# gripper-board-rev1.net
KiCad netlist of a schematic drawn in EAGLE
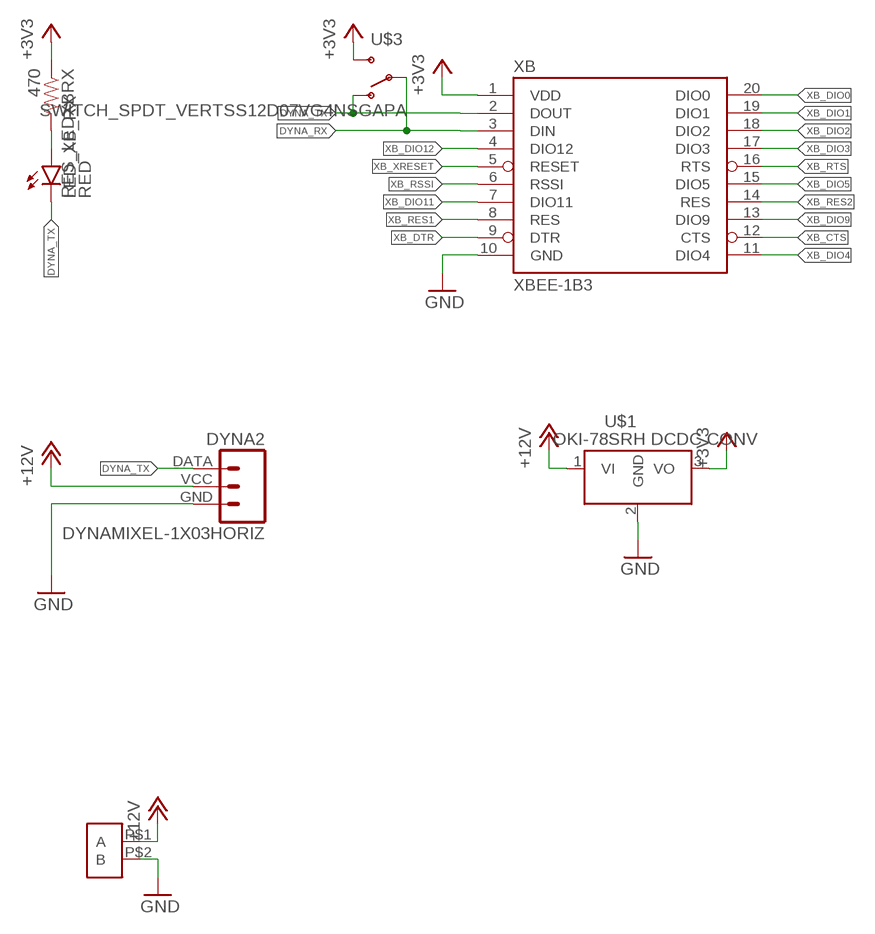
[diagram p0: schematic, sheet 1]

(export (version "E")
  (design (tool "Eeschema 10.0.6"))
  (components
    (comp (ref "DYNA2")
      (value "DYNAMIXEL-1X03HORIZ")
      (footprint "eagle-import:MLX-SPOX5268-3PIN")
      (fields (field (name "MFR") "Molex"))
      (libsource (lib "eagle-import") (part "DYNAMIXEL-1X03HORIZ"))
    )
    (comp (ref "LED_XB_RX")
      (value "RED")
      (footprint "eagle-import:LED-1206")
      (libsource (lib "eagle-import") (part "LED1206"))
    )
    (comp (ref "RES_LEDXBRX")
      (value "470")
      (footprint "eagle-import:1206")
      (libsource (lib "eagle-import") (part "RESISTOR1206"))
    )
    (comp (ref "U$1")
      (value "Q_OKI-78SR")
      (footprint "eagle-import:OKI-78SR_HORIZ")
      (libsource (lib "eagle-import") (part "Q_OKI-78SR"))
    )
    (comp (ref "U$2")
      (value "2POS_TERM_BLOCKPHOENIX-1935161")
      (footprint "eagle-import:PHOENIX-1935161")
      (libsource (lib "eagle-import") (part "2POS_TERM_BLOCKPHOENIX-1935161"))
    )
    (comp (ref "U$3")
      (value "SWITCH_SPDT_VERTSS12D07VG4NSGAPA")
      (footprint "eagle-import:C&K-SS12D07VG4NSGAPA")
      (libsource (lib "eagle-import") (part "SWITCH_SPDT_VERTSS12D07VG4NSGAPA"))
    )
    (comp (ref "XB")
      (value "XBEE-1B3")
      (footprint "eagle-import:XBEE-SMD")
      (libsource (lib "eagle-import") (part "XBEE-1B3"))
    )
  )
  (nets
    (net (code "1") (name "+3V3") (class "Default")
      (node (ref "RES_LEDXBRX") (pin "1") (pinfunction "1_1") (pintype "passive"))
      (node (ref "U$1") (pin "3") (pinfunction "VO_3") (pintype "bidirectional"))
      (node (ref "U$3") (pin "P$3") (pinfunction "S_P$3") (pintype "passive"))
      (node (ref "XB") (pin "1") (pinfunction "VDD_1") (pintype "power_in"))
    )
    (net (code "2") (name "+12V") (class "Default")
      (node (ref "DYNA2") (pin "VCC") (pinfunction "VCC_VCC") (pintype "passive"))
      (node (ref "U$1") (pin "1") (pinfunction "VI_1") (pintype "bidirectional"))
      (node (ref "U$2") (pin "P$1") (pinfunction "A_P$1") (pintype "bidirectional"))
    )
    (net (code "3") (name "DYNA_RX") (class "Default")
      (node (ref "U$3") (pin "P$2") (pinfunction "P_P$2") (pintype "passive"))
      (node (ref "XB") (pin "3") (pinfunction "DIN_3") (pintype "input"))
    )
    (net (code "4") (name "DYNA_TX") (class "Default")
      (node (ref "DYNA2") (pin "DATA") (pinfunction "DATA_DATA") (pintype "passive"))
      (node (ref "LED_XB_RX") (pin "C") (pinfunction "C_C") (pintype "passive"))
      (node (ref "U$3") (pin "P$1") (pinfunction "O_P$1") (pintype "passive"))
      (node (ref "XB") (pin "2") (pinfunction "DOUT_2") (pintype "output"))
    )
    (net (code "5") (name "GND") (class "Default")
      (node (ref "DYNA2") (pin "GND") (pinfunction "GND_GND") (pintype "passive"))
      (node (ref "U$1") (pin "2") (pinfunction "GND_2") (pintype "bidirectional"))
      (node (ref "U$2") (pin "P$2") (pinfunction "B_P$2") (pintype "bidirectional"))
      (node (ref "XB") (pin "10") (pinfunction "GND_10") (pintype "power_in"))
    )
    (net (code "6") (name "Net-(LED_XB_RX-PadA)") (class "Default")
      (node (ref "LED_XB_RX") (pin "A") (pinfunction "A_A") (pintype "passive"))
      (node (ref "RES_LEDXBRX") (pin "2") (pinfunction "2_2") (pintype "passive"))
    )
    (net (code "7") (name "XB_CTS") (class "Default")
      (node (ref "XB") (pin "12") (pinfunction "CTS_12") (pintype "output"))
    )
    (net (code "8") (name "XB_DIO0") (class "Default")
      (node (ref "XB") (pin "20") (pinfunction "DIO0_20") (pintype "bidirectional"))
    )
    (net (code "9") (name "XB_DIO1") (class "Default")
      (node (ref "XB") (pin "19") (pinfunction "DIO1_19") (pintype "bidirectional"))
    )
    (net (code "10") (name "XB_DIO2") (class "Default")
      (node (ref "XB") (pin "18") (pinfunction "DIO2_18") (pintype "bidirectional"))
    )
    (net (code "11") (name "XB_DIO3") (class "Default")
      (node (ref "XB") (pin "17") (pinfunction "DIO3_17") (pintype "bidirectional"))
    )
    (net (code "12") (name "XB_DIO4") (class "Default")
      (node (ref "XB") (pin "11") (pinfunction "DIO4_11") (pintype "bidirectional"))
    )
    (net (code "13") (name "XB_DIO5") (class "Default")
      (node (ref "XB") (pin "15") (pinfunction "DIO5_15") (pintype "bidirectional"))
    )
    (net (code "14") (name "XB_DIO9") (class "Default")
      (node (ref "XB") (pin "13") (pinfunction "DIO9_13") (pintype "bidirectional"))
    )
    (net (code "15") (name "XB_DIO11") (class "Default")
      (node (ref "XB") (pin "7") (pinfunction "DIO11_7") (pintype "bidirectional"))
    )
    (net (code "16") (name "XB_DIO12") (class "Default")
      (node (ref "XB") (pin "4") (pinfunction "DIO12_4") (pintype "bidirectional"))
    )
    (net (code "17") (name "XB_DTR") (class "Default")
      (node (ref "XB") (pin "9") (pinfunction "DTR_9") (pintype "bidirectional"))
    )
    (net (code "18") (name "XB_RES1") (class "Default")
      (node (ref "XB") (pin "8") (pinfunction "RES_8") (pintype "bidirectional"))
    )
    (net (code "19") (name "XB_RES2") (class "Default")
      (node (ref "XB") (pin "14") (pinfunction "RES_14") (pintype "bidirectional"))
    )
    (net (code "20") (name "XB_RSSI") (class "Default")
      (node (ref "XB") (pin "6") (pinfunction "RSSI_6") (pintype "bidirectional"))
    )
    (net (code "21") (name "XB_RTS") (class "Default")
      (node (ref "XB") (pin "16") (pinfunction "RTS_16") (pintype "input"))
    )
    (net (code "22") (name "XB_XRESET") (class "Default")
      (node (ref "XB") (pin "5") (pinfunction "RESET_5") (pintype "input"))
    )
  )
)
